# power.net
KiCad netlist of a schematic drawn in EAGLE
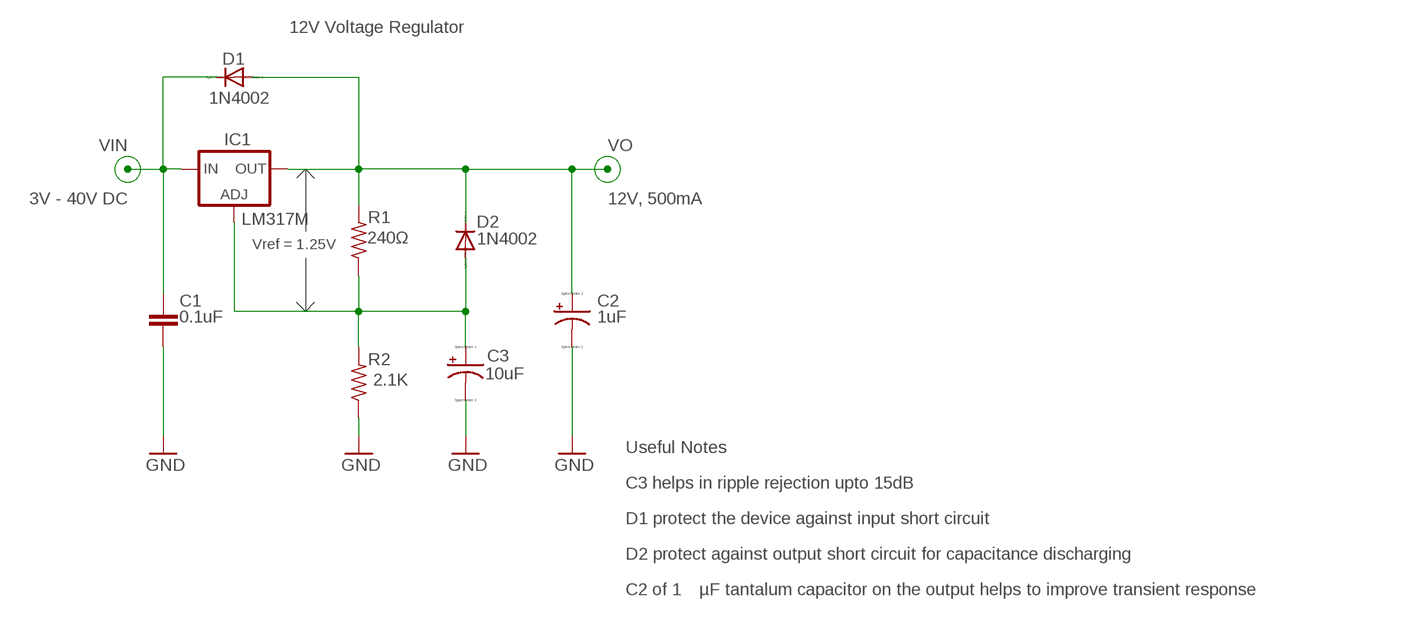
[diagram p0: schematic, sheet 1]

(export (version "E")
  (design (tool "Eeschema 10.0.6"))
  (components
    (comp (ref "C1")
      (value "0.1uF")
      (footprint "eagle-import:C075-052X106")
      (libsource (lib "eagle-import") (part "C-EU075-052X106"))
    )
    (comp (ref "C2")
      (value "1uF")
      (footprint "eagle-import:085CS_1AR")
      (libsource (lib "eagle-import") (part "CPOL-US085CS-1AR"))
    )
    (comp (ref "C3")
      (value "10uF")
      (footprint "eagle-import:085CS_1AR")
      (libsource (lib "eagle-import") (part "CPOL-US085CS-1AR"))
    )
    (comp (ref "D1")
      (value "1N4002")
      (footprint "eagle-import:DO41-10")
      (libsource (lib "eagle-import") (part "1N4004"))
    )
    (comp (ref "D2")
      (value "1N4002")
      (footprint "eagle-import:DO41-10")
      (libsource (lib "eagle-import") (part "1N4004"))
    )
    (comp (ref "IC1")
      (value "LM317MBSTT3")
      (footprint "eagle-import:SOT223")
      (fields (field (name "PARTNUMBER") "LM317M"))
      (libsource (lib "eagle-import") (part "LM317?MBSTT3"))
    )
    (comp (ref "R1")
      (value "240Ω")
      (footprint "eagle-import:M0805")
      (libsource (lib "eagle-import") (part "R-US_M0805"))
    )
    (comp (ref "R2")
      (value "2.1K")
      (footprint "eagle-import:M0805")
      (libsource (lib "eagle-import") (part "R-US_M0805"))
    )
  )
  (nets
    (net (code "1") (name "/VIN") (class "Default")
      (node (ref "C1") (pin "1") (pinfunction "1_1") (pintype "passive"))
      (node (ref "D1") (pin "C") (pinfunction "C_C") (pintype "passive"))
      (node (ref "IC1") (pin "3") (pinfunction "IN_3") (pintype "input"))
    )
    (net (code "2") (name "/VO") (class "Default")
      (node (ref "C2") (pin "+") (pinfunction "+_+") (pintype "passive"))
      (node (ref "D1") (pin "A") (pinfunction "A_A") (pintype "passive"))
      (node (ref "D2") (pin "C") (pinfunction "C_C") (pintype "passive"))
      (node (ref "IC1") (pin "4") (pinfunction "OUT_4") (pintype "passive"))
      (node (ref "R1") (pin "2") (pinfunction "2_2") (pintype "passive"))
    )
    (net (code "3") (name "GND") (class "Default")
      (node (ref "C1") (pin "2") (pinfunction "2_2") (pintype "passive"))
      (node (ref "C2") (pin "-") (pinfunction "-_-") (pintype "passive"))
      (node (ref "C3") (pin "-") (pinfunction "-_-") (pintype "passive"))
      (node (ref "R2") (pin "1") (pinfunction "1_1") (pintype "passive"))
    )
    (net (code "4") (name "Net-(IC1-ADJ)") (class "Default")
      (node (ref "C3") (pin "+") (pinfunction "+_+") (pintype "passive"))
      (node (ref "D2") (pin "A") (pinfunction "A_A") (pintype "passive"))
      (node (ref "IC1") (pin "1") (pinfunction "ADJ_1") (pintype "input"))
      (node (ref "R1") (pin "1") (pinfunction "1_1") (pintype "passive"))
      (node (ref "R2") (pin "2") (pinfunction "2_2") (pintype "passive"))
    )
  )
)
